# Sonar_Sheet1.net
KiCad netlist of a schematic drawn in Altium Designer
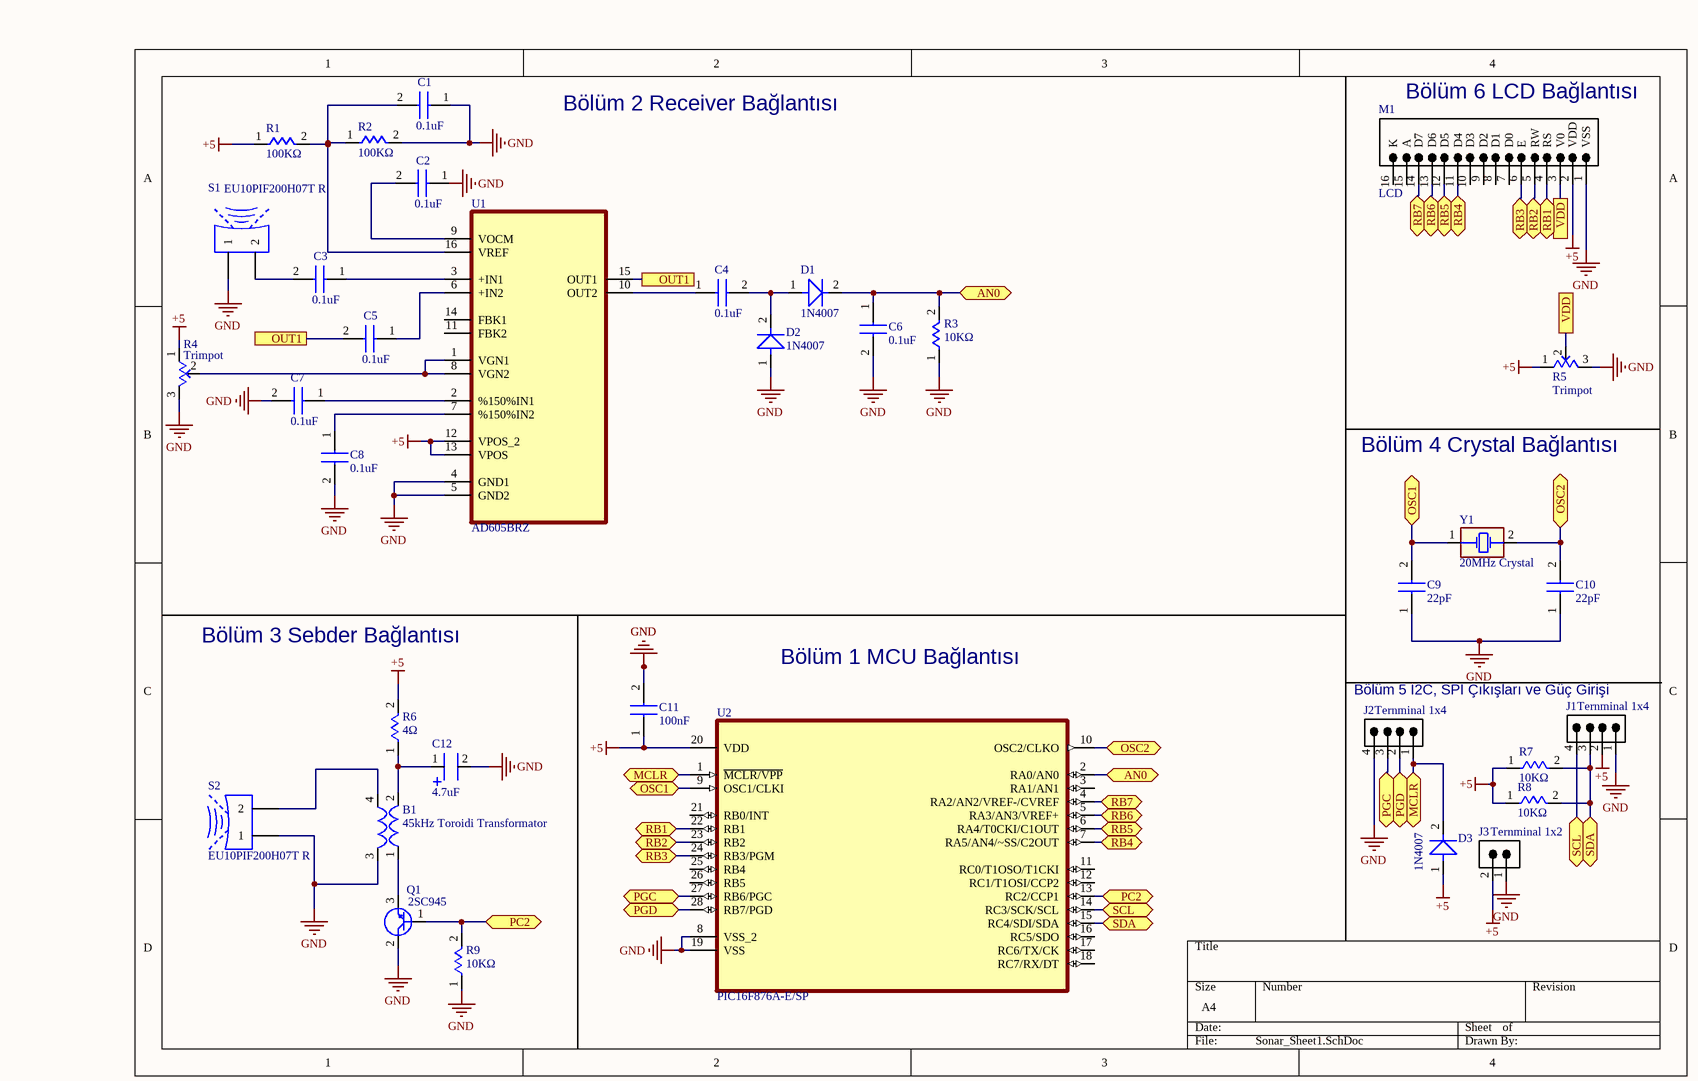
[diagram p0: Sonar_Sheet1.SchDoc]

(export (version "E")
  (design (tool "Eeschema 10.0.6"))
  (components
    (comp (ref "B1")
      (value "45kHz Toroidi Transformator")
      (footprint "Toroidi Transformator")
      (description "Toroidi Transformator")
      (libsource (lib "Sonar_Schlib1") (part "45kHz Toroidi Transformator"))
    )
    (comp (ref "C1")
      (value "0.1uF")
      (footprint "CAP")
      (description "Capacitor")
      (libsource (lib "Sonar_Schlib1") (part "CAP"))
    )
    (comp (ref "C2")
      (value "0.1uF")
      (footprint "CAP")
      (description "Capacitor")
      (libsource (lib "Sonar_Schlib1") (part "CAP"))
    )
    (comp (ref "C3")
      (value "0.1uF")
      (footprint "CAP")
      (description "Capacitor")
      (libsource (lib "Sonar_Schlib1") (part "CAP"))
    )
    (comp (ref "C4")
      (value "0.1uF")
      (footprint "CAP")
      (description "Capacitor")
      (libsource (lib "Sonar_Schlib1") (part "CAP"))
    )
    (comp (ref "C5")
      (value "0.1uF")
      (footprint "CAP")
      (description "Capacitor")
      (libsource (lib "Sonar_Schlib1") (part "CAP"))
    )
    (comp (ref "C6")
      (value "0.1uF")
      (footprint "CAP")
      (description "Capacitor")
      (libsource (lib "Sonar_Schlib1") (part "CAP"))
    )
    (comp (ref "C7")
      (value "0.1uF")
      (footprint "CAP")
      (description "Capacitor")
      (libsource (lib "Sonar_Schlib1") (part "CAP"))
    )
    (comp (ref "C8")
      (value "0.1uF")
      (footprint "CAP")
      (description "Capacitor")
      (libsource (lib "Sonar_Schlib1") (part "CAP"))
    )
    (comp (ref "C9")
      (value "22pF")
      (footprint "CAP")
      (description "Capacitor")
      (libsource (lib "Sonar_Schlib1") (part "CAP"))
    )
    (comp (ref "C10")
      (value "22pF")
      (footprint "CAP")
      (description "Capacitor")
      (libsource (lib "Sonar_Schlib1") (part "CAP"))
    )
    (comp (ref "C11")
      (value "100nF")
      (footprint "CAP")
      (description "Capacitor")
      (libsource (lib "Sonar_Schlib1") (part "CAP"))
    )
    (comp (ref "C12")
      (value "4.7uF")
      (footprint "CAP POL")
      (description "MZ1V687M12020PH - CAP.EL.680uF 35V 12.5x20 5MM 105C TB SAMWHA")
      (libsource (lib "Sonar_Schlib1") (part "Cap Pol"))
    )
    (comp (ref "D1")
      (value "1N4007")
      (footprint "Diode")
      (description "1N4007 Diyot - MIC")
      (libsource (lib "Sonar_Schlib1") (part "1N4007"))
    )
    (comp (ref "D2")
      (value "1N4007")
      (footprint "Diode")
      (description "1N4007 Diyot - MIC")
      (libsource (lib "Sonar_Schlib1") (part "1N4007"))
    )
    (comp (ref "D3")
      (value "1N4007")
      (footprint "Diode")
      (description "1N4007 Diyot - MIC")
      (libsource (lib "Sonar_Schlib1") (part "1N4007"))
    )
    (comp (ref "J1")
      (value "Ternminal 1x4")
      (footprint "Terminal 1x4")
      (libsource (lib "Sonar_Schlib1") (part "Ternminal 1x4"))
    )
    (comp (ref "J2")
      (value "Ternminal 1x4")
      (footprint "Terminal 1x4")
      (libsource (lib "Sonar_Schlib1") (part "Ternminal 1x4"))
    )
    (comp (ref "J3")
      (value "Ternminal 1x2")
      (footprint "Terminal 1x2")
      (libsource (lib "Sonar_Schlib1") (part "Ternminal 1x2"))
    )
    (comp (ref "M1")
      (value "LCD")
      (footprint "LCD")
      (description "2x16 LCD Ekran Sol Üst Mavi - Qapass")
      (libsource (lib "Sonar_Schlib1") (part "LCD"))
    )
    (comp (ref "Q1")
      (value "2SC945")
      (footprint "2SC945")
      (description "2SC945 Npn Tht Transistör To-92")
      (libsource (lib "Sonar_Schlib1") (part "2SC945"))
    )
    (comp (ref "R1")
      (value "100KΩ")
      (footprint "Res")
      (description "THT RES")
      (libsource (lib "Sonar_Schlib1") (part "RES"))
    )
    (comp (ref "R2")
      (value "100KΩ")
      (footprint "Res")
      (description "THT RES")
      (libsource (lib "Sonar_Schlib1") (part "RES"))
    )
    (comp (ref "R3")
      (value "10KΩ")
      (footprint "Res")
      (description "THT RES")
      (libsource (lib "Sonar_Schlib1") (part "RES"))
    )
    (comp (ref "R4")
      (value "Trimpot")
      (footprint "Trimpot")
      (description "10K Trimpot (Yatık) - PT10")
      (libsource (lib "Sonar_Schlib1") (part "Trimpot"))
    )
    (comp (ref "R5")
      (value "Trimpot")
      (footprint "Trimpot")
      (description "10K Trimpot (Yatık) - PT10")
      (libsource (lib "Sonar_Schlib1") (part "Trimpot"))
    )
    (comp (ref "R6")
      (value "4Ω")
      (footprint "Res")
      (description "THT RES")
      (libsource (lib "Sonar_Schlib1") (part "RES"))
    )
    (comp (ref "R7")
      (value "10KΩ")
      (footprint "Res")
      (description "THT RES")
      (libsource (lib "Sonar_Schlib1") (part "RES"))
    )
    (comp (ref "R8")
      (value "10KΩ")
      (footprint "Res")
      (description "THT RES")
      (libsource (lib "Sonar_Schlib1") (part "RES"))
    )
    (comp (ref "R9")
      (value "10KΩ")
      (footprint "Res")
      (description "THT RES")
      (libsource (lib "Sonar_Schlib1") (part "RES"))
    )
    (comp (ref "S1")
      (value "EU10PIF200H07T R")
      (footprint "EU10PIF200H07T R")
      (description "Suya Dayanıklı Ultrasonik Sensör RT Mesafe Ölçüm Probu - 10mm (EU10PIF200H07T R 200Khz)")
      (libsource (lib "Sonar_Schlib1") (part "EU10PIF200H07T R"))
    )
    (comp (ref "S2")
      (value "EU10PIF200H07T R")
      (footprint "EU10PIF200H07T R")
      (description "Suya Dayanıklı Ultrasonik Sensör RT Mesafe Ölçüm Probu - 10mm (EU10PIF200H07T R 200Khz)")
      (libsource (lib "Sonar_Schlib1") (part "EU10PIF200H07T R"))
    )
    (comp (ref "U1")
      (value "AD605BRZ")
      (footprint "SOIC127P600X175-16N")
      (description "SP Amp Variable Gain Amp Dual 5.5V 16-Pin SOIC N Tube")
      (fields (field (name "MF") "Analog Devices"))
      (libsource (lib "Sonar_Schlib1") (part "AD605BRZ"))
    )
    (comp (ref "U2")
      (value "PIC16F876A-E/SP")
      (footprint "DIP787W46P254L3467H508Q28")
      (description "PIC PICÂ® 16F Microcontroller IC 8-Bit 20MHz 14KB _8K x 14_ FLASH 28-SPDIP")
      (fields (field (name "MF") "Microchip"))
      (libsource (lib "Sonar_Schlib1") (part "PIC16F876A-E/SP"))
    )
    (comp (ref "Y1")
      (value "20MHz Crystal")
      (footprint "Crystal")
      (description "20.000 MHz Kristal HC-49S")
      (libsource (lib "Sonar_Schlib1") (part "20MHz Crystal"))
    )
  )
  (nets
    (net (code "1") (name "+5") (class "Default")
      (node (ref "C11") (pin "1") (pinfunction "1_1") (pintype "passive"))
      (node (ref "D3") (pin "1") (pinfunction "1_1") (pintype "passive"))
      (node (ref "J1") (pin "2") (pinfunction "2_2") (pintype "passive"))
      (node (ref "J3") (pin "2") (pinfunction "2_2") (pintype "passive"))
      (node (ref "M1") (pin "2") (pinfunction "VDD_2") (pintype "passive"))
      (node (ref "R1") (pin "1") (pinfunction "1_1") (pintype "passive"))
      (node (ref "R4") (pin "1") (pinfunction "1_1") (pintype "power_in"))
      (node (ref "R5") (pin "1") (pinfunction "1_1") (pintype "power_in"))
      (node (ref "R6") (pin "2") (pinfunction "2_2") (pintype "passive"))
      (node (ref "R7") (pin "1") (pinfunction "1_1") (pintype "passive"))
      (node (ref "R8") (pin "1") (pinfunction "1_1") (pintype "passive"))
      (node (ref "U1") (pin "12") (pinfunction "VPOS_2_12") (pintype "power_in"))
      (node (ref "U1") (pin "13") (pinfunction "VPOS_13") (pintype "power_in"))
      (node (ref "U2") (pin "20") (pinfunction "VDD_20") (pintype "power_in"))
    )
    (net (code "2") (name "/AN0") (class "Default")
      (node (ref "C6") (pin "1") (pinfunction "1_1") (pintype "passive"))
      (node (ref "D1") (pin "2") (pinfunction "2_2") (pintype "passive"))
      (node (ref "R3") (pin "2") (pinfunction "2_2") (pintype "passive"))
      (node (ref "U2") (pin "2") (pinfunction "RA0/AN0_2") (pintype "bidirectional"))
    )
    (net (code "3") (name "/MCLR") (class "Default")
      (node (ref "D3") (pin "2") (pinfunction "2_2") (pintype "passive"))
      (node (ref "J2") (pin "1") (pinfunction "1_1") (pintype "passive"))
      (node (ref "U2") (pin "1") (pinfunction "~{MCLR/VPP}_1") (pintype "input"))
    )
    (net (code "4") (name "/OSC1") (class "Default")
      (node (ref "C9") (pin "2") (pinfunction "2_2") (pintype "passive"))
      (node (ref "U2") (pin "9") (pinfunction "OSC1/CLKI_9") (pintype "input"))
      (node (ref "Y1") (pin "1") (pinfunction "1_1") (pintype "power_in"))
    )
    (net (code "5") (name "/OSC2") (class "Default")
      (node (ref "C10") (pin "2") (pinfunction "2_2") (pintype "passive"))
      (node (ref "U2") (pin "10") (pinfunction "OSC2/CLKO_10") (pintype "output"))
      (node (ref "Y1") (pin "2") (pinfunction "2_2") (pintype "power_in"))
    )
    (net (code "6") (name "/OUT1") (class "Default")
      (node (ref "C5") (pin "2") (pinfunction "2_2") (pintype "passive"))
      (node (ref "U1") (pin "15") (pinfunction "OUT1_15") (pintype "passive"))
    )
    (net (code "7") (name "/PC2") (class "Default")
      (node (ref "Q1") (pin "1") (pinfunction "1_1") (pintype "power_in"))
      (node (ref "R9") (pin "2") (pinfunction "2_2") (pintype "passive"))
      (node (ref "U2") (pin "13") (pinfunction "RC2/CCP1_13") (pintype "bidirectional"))
    )
    (net (code "8") (name "/PGC") (class "Default")
      (node (ref "J2") (pin "3") (pinfunction "3_3") (pintype "passive"))
      (node (ref "U2") (pin "27") (pinfunction "RB6/PGC_27") (pintype "bidirectional"))
    )
    (net (code "9") (name "/PGD") (class "Default")
      (node (ref "J2") (pin "2") (pinfunction "2_2") (pintype "passive"))
      (node (ref "U2") (pin "28") (pinfunction "RB7/PGD_28") (pintype "bidirectional"))
    )
    (net (code "10") (name "/RB1") (class "Default")
      (node (ref "M1") (pin "4") (pinfunction "RS_4") (pintype "passive"))
      (node (ref "U2") (pin "22") (pinfunction "RB1_22") (pintype "bidirectional"))
    )
    (net (code "11") (name "/RB2") (class "Default")
      (node (ref "M1") (pin "5") (pinfunction "RW_5") (pintype "passive"))
      (node (ref "U2") (pin "23") (pinfunction "RB2_23") (pintype "bidirectional"))
    )
    (net (code "12") (name "/RB3") (class "Default")
      (node (ref "M1") (pin "6") (pinfunction "E_6") (pintype "passive"))
      (node (ref "U2") (pin "24") (pinfunction "RB3/PGM_24") (pintype "bidirectional"))
    )
    (net (code "13") (name "/RB4") (class "Default")
      (node (ref "M1") (pin "11") (pinfunction "D4_11") (pintype "passive"))
      (node (ref "U2") (pin "7") (pinfunction "RA5/AN4/~SS/C2OUT_7") (pintype "bidirectional"))
    )
    (net (code "14") (name "/RB5") (class "Default")
      (node (ref "M1") (pin "12") (pinfunction "D5_12") (pintype "passive"))
      (node (ref "U2") (pin "6") (pinfunction "RA4/T0CKI/C1OUT_6") (pintype "bidirectional"))
    )
    (net (code "15") (name "/RB6") (class "Default")
      (node (ref "M1") (pin "13") (pinfunction "D6_13") (pintype "passive"))
      (node (ref "U2") (pin "5") (pinfunction "RA3/AN3/VREF+_5") (pintype "bidirectional"))
    )
    (net (code "16") (name "/RB7") (class "Default")
      (node (ref "M1") (pin "14") (pinfunction "D7_14") (pintype "passive"))
      (node (ref "U2") (pin "4") (pinfunction "RA2/AN2/VREF-/CVREF_4") (pintype "bidirectional"))
    )
    (net (code "17") (name "/SCL") (class "Default")
      (node (ref "J1") (pin "4") (pinfunction "4_4") (pintype "passive"))
      (node (ref "U2") (pin "14") (pinfunction "RC3/SCK/SCL_14") (pintype "bidirectional"))
    )
    (net (code "18") (name "/SDA") (class "Default")
      (node (ref "J1") (pin "3") (pinfunction "3_3") (pintype "passive"))
      (node (ref "R7") (pin "2") (pinfunction "2_2") (pintype "passive"))
      (node (ref "R8") (pin "2") (pinfunction "2_2") (pintype "passive"))
      (node (ref "U2") (pin "15") (pinfunction "RC4/SDI/SDA_15") (pintype "bidirectional"))
    )
    (net (code "19") (name "/VDD") (class "Default")
      (node (ref "M1") (pin "3") (pinfunction "V0_3") (pintype "passive"))
      (node (ref "R5") (pin "2") (pinfunction "2_2") (pintype "power_in"))
    )
    (net (code "20") (name "GND") (class "Default")
      (node (ref "B1") (pin "3") (pinfunction "3_3") (pintype "power_in"))
      (node (ref "C1") (pin "1") (pinfunction "1_1") (pintype "passive"))
      (node (ref "C10") (pin "1") (pinfunction "1_1") (pintype "passive"))
      (node (ref "C11") (pin "2") (pinfunction "2_2") (pintype "passive"))
      (node (ref "C12") (pin "2") (pinfunction "2_2") (pintype "passive"))
      (node (ref "C2") (pin "1") (pinfunction "1_1") (pintype "passive"))
      (node (ref "C6") (pin "2") (pinfunction "2_2") (pintype "passive"))
      (node (ref "C7") (pin "2") (pinfunction "2_2") (pintype "passive"))
      (node (ref "C8") (pin "2") (pinfunction "2_2") (pintype "passive"))
      (node (ref "C9") (pin "1") (pinfunction "1_1") (pintype "passive"))
      (node (ref "D2") (pin "1") (pinfunction "1_1") (pintype "passive"))
      (node (ref "J1") (pin "1") (pinfunction "1_1") (pintype "passive"))
      (node (ref "J2") (pin "4") (pinfunction "4_4") (pintype "passive"))
      (node (ref "J3") (pin "1") (pinfunction "1_1") (pintype "passive"))
      (node (ref "M1") (pin "1") (pinfunction "VSS_1") (pintype "passive"))
      (node (ref "Q1") (pin "2") (pinfunction "2_2") (pintype "power_in"))
      (node (ref "R2") (pin "2") (pinfunction "2_2") (pintype "passive"))
      (node (ref "R3") (pin "1") (pinfunction "1_1") (pintype "passive"))
      (node (ref "R4") (pin "3") (pinfunction "3_3") (pintype "power_in"))
      (node (ref "R5") (pin "3") (pinfunction "3_3") (pintype "power_in"))
      (node (ref "R9") (pin "1") (pinfunction "1_1") (pintype "passive"))
      (node (ref "S1") (pin "1") (pinfunction "1_1") (pintype "passive"))
      (node (ref "S2") (pin "1") (pinfunction "1_1") (pintype "passive"))
      (node (ref "U1") (pin "4") (pinfunction "GND1_4") (pintype "passive"))
      (node (ref "U1") (pin "5") (pinfunction "GND2_5") (pintype "passive"))
      (node (ref "U2") (pin "19") (pinfunction "VSS_19") (pintype "power_in"))
      (node (ref "U2") (pin "8") (pinfunction "VSS_2_8") (pintype "power_in"))
    )
    (net (code "21") (name "Net-(B1-Pad1)") (class "Default")
      (node (ref "B1") (pin "1") (pinfunction "1_1") (pintype "power_in"))
      (node (ref "Q1") (pin "3") (pinfunction "3_3") (pintype "power_in"))
    )
    (net (code "22") (name "Net-(B1-Pad2)") (class "Default")
      (node (ref "B1") (pin "2") (pinfunction "2_2") (pintype "power_in"))
      (node (ref "C12") (pin "1") (pinfunction "1_1") (pintype "passive"))
      (node (ref "R6") (pin "1") (pinfunction "1_1") (pintype "passive"))
    )
    (net (code "23") (name "Net-(B1-Pad4)") (class "Default")
      (node (ref "B1") (pin "4") (pinfunction "4_4") (pintype "power_in"))
      (node (ref "S2") (pin "2") (pinfunction "2_2") (pintype "passive"))
    )
    (net (code "24") (name "Net-(C3-Pad2)") (class "Default")
      (node (ref "C3") (pin "2") (pinfunction "2_2") (pintype "passive"))
      (node (ref "S1") (pin "2") (pinfunction "2_2") (pintype "passive"))
    )
    (net (code "25") (name "Net-(C4-Pad2)") (class "Default")
      (node (ref "C4") (pin "2") (pinfunction "2_2") (pintype "passive"))
      (node (ref "D1") (pin "1") (pinfunction "1_1") (pintype "passive"))
      (node (ref "D2") (pin "2") (pinfunction "2_2") (pintype "passive"))
    )
    (net (code "26") (name "Net-(U1-%150%IN1)") (class "Default")
      (node (ref "C7") (pin "1") (pinfunction "1_1") (pintype "passive"))
      (node (ref "U1") (pin "2") (pinfunction "%150%IN1_2") (pintype "passive"))
    )
    (net (code "27") (name "Net-(U1-%150%IN2)") (class "Default")
      (node (ref "C8") (pin "1") (pinfunction "1_1") (pintype "passive"))
      (node (ref "U1") (pin "7") (pinfunction "%150%IN2_7") (pintype "passive"))
    )
    (net (code "28") (name "Net-(U1-+IN1)") (class "Default")
      (node (ref "C3") (pin "1") (pinfunction "1_1") (pintype "passive"))
      (node (ref "U1") (pin "3") (pinfunction "+IN1_3") (pintype "passive"))
    )
    (net (code "29") (name "Net-(U1-+IN2)") (class "Default")
      (node (ref "C5") (pin "1") (pinfunction "1_1") (pintype "passive"))
      (node (ref "U1") (pin "6") (pinfunction "+IN2_6") (pintype "passive"))
    )
    (net (code "30") (name "Net-(U1-OUT2)") (class "Default")
      (node (ref "C4") (pin "1") (pinfunction "1_1") (pintype "passive"))
      (node (ref "U1") (pin "10") (pinfunction "OUT2_10") (pintype "passive"))
    )
    (net (code "31") (name "Net-(U1-VGN1)") (class "Default")
      (node (ref "R4") (pin "2") (pinfunction "2_2") (pintype "power_in"))
      (node (ref "U1") (pin "1") (pinfunction "VGN1_1") (pintype "passive"))
      (node (ref "U1") (pin "8") (pinfunction "VGN2_8") (pintype "passive"))
    )
    (net (code "32") (name "Net-(U1-VOCM)") (class "Default")
      (node (ref "C2") (pin "2") (pinfunction "2_2") (pintype "passive"))
      (node (ref "U1") (pin "9") (pinfunction "VOCM_9") (pintype "passive"))
    )
    (net (code "33") (name "Net-(U1-VREF)") (class "Default")
      (node (ref "C1") (pin "2") (pinfunction "2_2") (pintype "passive"))
      (node (ref "R1") (pin "2") (pinfunction "2_2") (pintype "passive"))
      (node (ref "R2") (pin "1") (pinfunction "1_1") (pintype "passive"))
      (node (ref "U1") (pin "16") (pinfunction "VREF_16") (pintype "passive"))
    )
    (net (code "34") (name "unconnected-(M1-A-Pad15)") (class "Default")
      (node (ref "M1") (pin "15") (pinfunction "A_15") (pintype "passive"))
    )
    (net (code "35") (name "unconnected-(M1-D0-Pad7)") (class "Default")
      (node (ref "M1") (pin "7") (pinfunction "D0_7") (pintype "passive"))
    )
    (net (code "36") (name "unconnected-(M1-D1-Pad8)") (class "Default")
      (node (ref "M1") (pin "8") (pinfunction "D1_8") (pintype "passive"))
    )
    (net (code "37") (name "unconnected-(M1-D2-Pad9)") (class "Default")
      (node (ref "M1") (pin "9") (pinfunction "D2_9") (pintype "passive"))
    )
    (net (code "38") (name "unconnected-(M1-D3-Pad10)") (class "Default")
      (node (ref "M1") (pin "10") (pinfunction "D3_10") (pintype "passive"))
    )
    (net (code "39") (name "unconnected-(M1-K-Pad16)") (class "Default")
      (node (ref "M1") (pin "16") (pinfunction "K_16") (pintype "passive"))
    )
    (net (code "40") (name "unconnected-(U1-FBK1-Pad14)") (class "Default")
      (node (ref "U1") (pin "14") (pinfunction "FBK1_14") (pintype "passive"))
    )
    (net (code "41") (name "unconnected-(U1-FBK2-Pad11)") (class "Default")
      (node (ref "U1") (pin "11") (pinfunction "FBK2_11") (pintype "passive"))
    )
    (net (code "42") (name "unconnected-(U2-RA1{slash}AN1-Pad3)") (class "Default")
      (node (ref "U2") (pin "3") (pinfunction "RA1/AN1_3") (pintype "bidirectional"))
    )
    (net (code "43") (name "unconnected-(U2-RB0{slash}INT-Pad21)") (class "Default")
      (node (ref "U2") (pin "21") (pinfunction "RB0/INT_21") (pintype "bidirectional"))
    )
    (net (code "44") (name "unconnected-(U2-RB4-Pad25)") (class "Default")
      (node (ref "U2") (pin "25") (pinfunction "RB4_25") (pintype "bidirectional"))
    )
    (net (code "45") (name "unconnected-(U2-RB5-Pad26)") (class "Default")
      (node (ref "U2") (pin "26") (pinfunction "RB5_26") (pintype "bidirectional"))
    )
    (net (code "46") (name "unconnected-(U2-RC0{slash}T1OSO{slash}T1CKI-Pad11)") (class "Default")
      (node (ref "U2") (pin "11") (pinfunction "RC0/T1OSO/T1CKI_11") (pintype "bidirectional"))
    )
    (net (code "47") (name "unconnected-(U2-RC1{slash}T1OSI{slash}CCP2-Pad12)") (class "Default")
      (node (ref "U2") (pin "12") (pinfunction "RC1/T1OSI/CCP2_12") (pintype "bidirectional"))
    )
    (net (code "48") (name "unconnected-(U2-RC5{slash}SDO-Pad16)") (class "Default")
      (node (ref "U2") (pin "16") (pinfunction "RC5/SDO_16") (pintype "bidirectional"))
    )
    (net (code "49") (name "unconnected-(U2-RC6{slash}TX{slash}CK-Pad17)") (class "Default")
      (node (ref "U2") (pin "17") (pinfunction "RC6/TX/CK_17") (pintype "bidirectional"))
    )
    (net (code "50") (name "unconnected-(U2-RC7{slash}RX{slash}DT-Pad18)") (class "Default")
      (node (ref "U2") (pin "18") (pinfunction "RC7/RX/DT_18") (pintype "bidirectional"))
    )
  )
)
